# PWR.net
KiCad netlist of a schematic drawn in Altium Designer
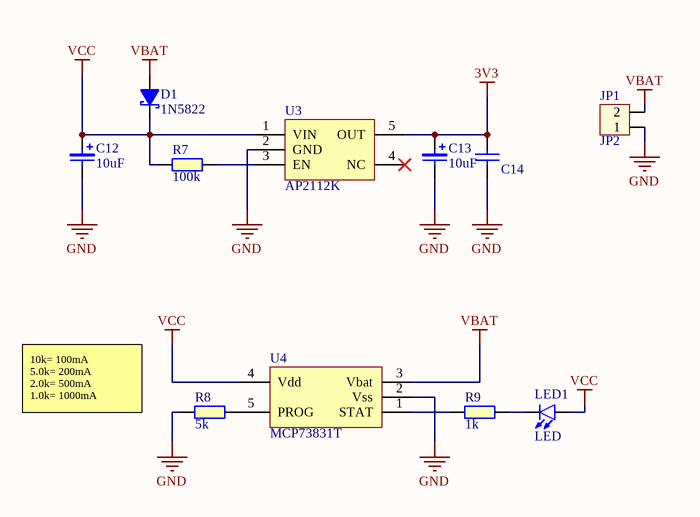
[diagram p0: PWR.SchDoc]

(export (version "E")
  (design (tool "Eeschema 10.0.6"))
  (components
    (comp (ref "C12")
      (value "10uF")
      (footprint "CASE A")
      (description "CAP TANT 10UF 16V 10% 2917")
      (fields (field (name "PART NUMBER") "T491A106K010AT") (field (name "VOLTAGE") "10VDC"))
      (libsource (lib "Node") (part "Capacitor-Tantalium"))
    )
    (comp (ref "C13")
      (value "10uF")
      (footprint "CASE A")
      (description "CAP TANT 10UF 16V 10% 2917")
      (fields (field (name "PART NUMBER") "T491A106K010AT") (field (name "VOLTAGE") "10VDC"))
      (libsource (lib "Node") (part "Capacitor-Tantalium"))
    )
    (comp (ref "C14") (value "0.01uF") (footprint "C_0603") (libsource (lib "Node") (part "CAP_0603")))
    (comp (ref "D1")
      (value "1N5822")
      (footprint "ThanhNT:DO-214AC")
      (description "3A 40V SS34")
      (libsource (lib "ThanhNT") (part "DIODE_1N5822"))
    )
    (comp (ref "JP1")
      (value "JP2")
      (footprint "CON2")
      (description "Connector 2")
      (libsource (lib "syhaunguyen") (part "Con2"))
    )
    (comp (ref "LED1") (value "LED") (footprint "LED_0603") (libsource (lib "Node") (part "LED_0603")))
    (comp (ref "R7") (value "100k") (footprint "R_0603") (libsource (lib "Node") (part "RES_0603")))
    (comp (ref "R8") (value "5k") (footprint "R_0603") (libsource (lib "Node") (part "RES_0603")))
    (comp (ref "R9") (value "1k") (footprint "R_0603") (libsource (lib "Node") (part "RES_0603")))
    (comp (ref "U3")
      (value "AP2112K")
      (footprint "SOT25")
      (description "IC REG LINEAR 3.3V 600MA SOT25")
      (fields
        (field (name "MANUFACTURER") "Diodes")
        (field (name "MANUFACTURER PART NUMBER") "AP2112K-3.3TRG1")
      )
      (libsource (lib "Node") (part "AP2112K"))
    )
    (comp (ref "U4")
      (value "MCP73831T")
      (footprint "SOT23-5")
      (description "IC CONTROLLR LI-ION 4.2V SOT23-5")
      (fields
        (field (name "MANUFACTURER") "Microchip")
        (field (name "MANUFACTURER PART NUMBER") "MCP73831T-2ACI/OT")
      )
      (libsource (lib "Node") (part "MCP73831T"))
    )
  )
  (nets
    (net (code "1") (name "3V3") (class "Default")
      (node (ref "C13") (pin "A") (pinfunction "A_A") (pintype "passive"))
      (node (ref "C14") (pin "2") (pinfunction "2_2") (pintype "passive"))
      (node (ref "U3") (pin "5") (pinfunction "OUT_5") (pintype "passive"))
    )
    (net (code "2") (name "GND") (class "Default")
      (node (ref "C12") (pin "K") (pinfunction "K_K") (pintype "passive"))
      (node (ref "C13") (pin "K") (pinfunction "K_K") (pintype "passive"))
      (node (ref "C14") (pin "1") (pinfunction "1_1") (pintype "passive"))
      (node (ref "JP1") (pin "1") (pinfunction "1_1") (pintype "passive"))
      (node (ref "R8") (pin "2") (pinfunction "2_2") (pintype "passive"))
      (node (ref "U3") (pin "2") (pinfunction "GND_2") (pintype "passive"))
      (node (ref "U4") (pin "2") (pinfunction "Vss_2") (pintype "passive"))
    )
    (net (code "3") (name "Net-(LED1-PadK)") (class "Default")
      (node (ref "LED1") (pin "K") (pinfunction "K_K") (pintype "passive"))
      (node (ref "R9") (pin "1") (pinfunction "1_1") (pintype "passive"))
    )
    (net (code "4") (name "Net-(U3-EN)") (class "Default")
      (node (ref "R7") (pin "1") (pinfunction "1_1") (pintype "passive"))
      (node (ref "U3") (pin "3") (pinfunction "EN_3") (pintype "passive"))
    )
    (net (code "5") (name "Net-(U4-PROG)") (class "Default")
      (node (ref "R8") (pin "1") (pinfunction "1_1") (pintype "passive"))
      (node (ref "U4") (pin "5") (pinfunction "PROG_5") (pintype "passive"))
    )
    (net (code "6") (name "Net-(U4-STAT)") (class "Default")
      (node (ref "R9") (pin "2") (pinfunction "2_2") (pintype "passive"))
      (node (ref "U4") (pin "1") (pinfunction "STAT_1") (pintype "passive"))
    )
    (net (code "7") (name "VBAT") (class "Default")
      (node (ref "D1") (pin "A") (pinfunction "A_A") (pintype "passive"))
      (node (ref "JP1") (pin "2") (pinfunction "2_2") (pintype "passive"))
      (node (ref "U4") (pin "3") (pinfunction "Vbat_3") (pintype "passive"))
    )
    (net (code "8") (name "VCC") (class "Default")
      (node (ref "C12") (pin "A") (pinfunction "A_A") (pintype "passive"))
      (node (ref "D1") (pin "K") (pinfunction "K_K") (pintype "passive"))
      (node (ref "LED1") (pin "A") (pinfunction "A_A") (pintype "passive"))
      (node (ref "R7") (pin "2") (pinfunction "2_2") (pintype "passive"))
      (node (ref "U3") (pin "1") (pinfunction "VIN_1") (pintype "passive"))
      (node (ref "U4") (pin "4") (pinfunction "Vdd_4") (pintype "passive"))
    )
    (net (code "9") (name "unconnected-(U3-NC-Pad4)") (class "Default")
      (node (ref "U3") (pin "4") (pinfunction "NC_4") (pintype "passive+no_connect"))
    )
  )
)
